# SparkFun_Artemis.net
KiCad netlist of a schematic drawn in EAGLE
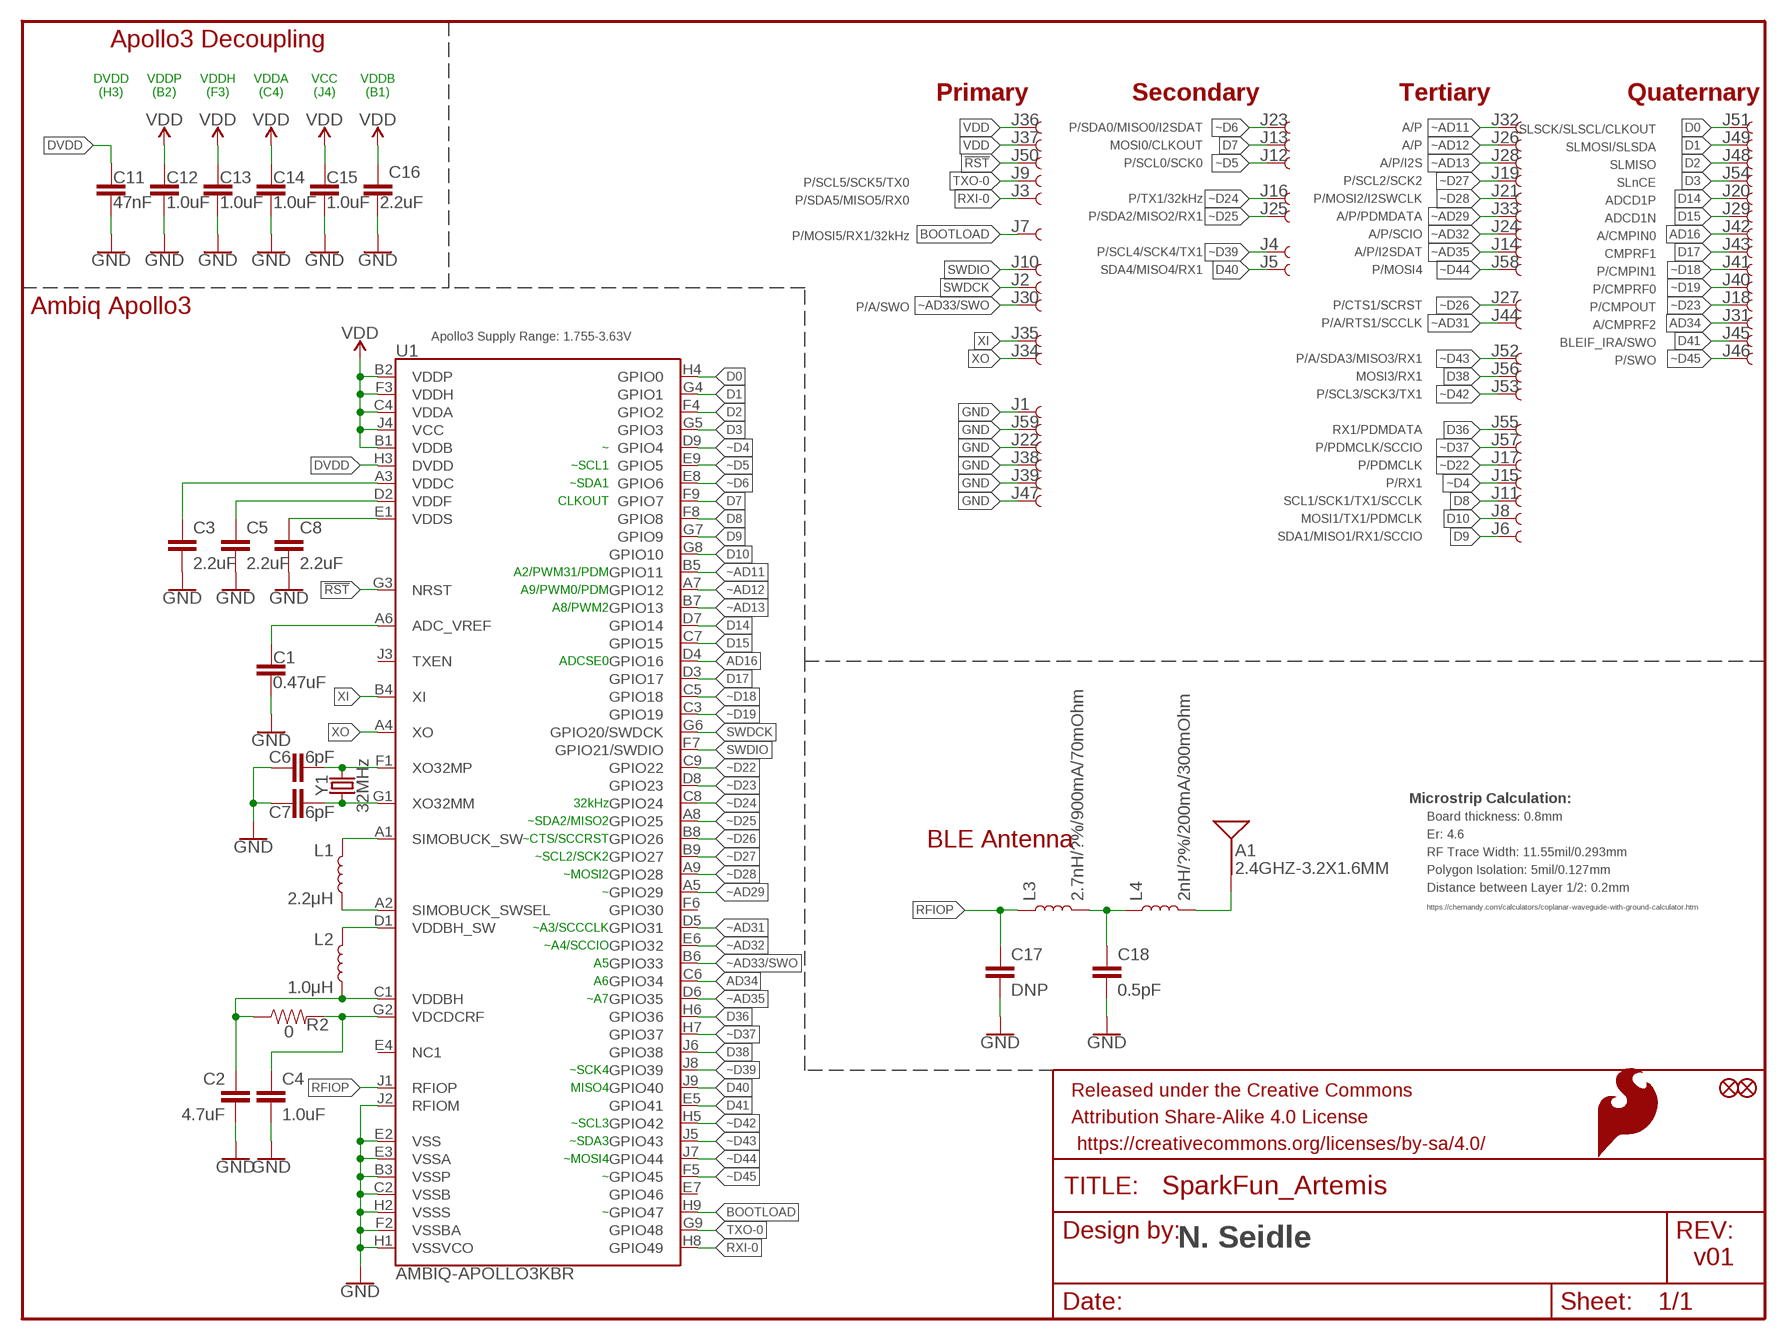
[diagram p0: schematic, sheet 1]

(export (version "E")
  (design (tool "Eeschema 10.0.6"))
  (components
    (comp (ref "A1")
      (value "2.4GHZ-3.2X1.6MM")
      (footprint "eagle-import:ANT-2.4GHZ-8.0X1.0MM")
      (libsource (lib "eagle-import") (part "ANTENNA2.4GHZ-8.0X1.0MM"))
    )
    (comp (ref "C1")
      (value "0.47uF")
      (footprint "eagle-import:0402-TIGHT")
      (libsource (lib "eagle-import") (part "470NF-0402_TIGHT-6.3V-10%-X5R"))
    )
    (comp (ref "C2")
      (value "4.7uF")
      (footprint "eagle-import:0402-TIGHT")
      (libsource (lib "eagle-import") (part "4.7UF-0402_TIGHT-6.3V-20%-X5R"))
    )
    (comp (ref "C3")
      (value "2.2uF")
      (footprint "eagle-import:0402-TIGHT")
      (libsource (lib "eagle-import") (part "2.2UF-0402_TIGHT-10V-10%-X5R"))
    )
    (comp (ref "C4")
      (value "1.0uF")
      (footprint "eagle-import:0402-TIGHT")
      (libsource (lib "eagle-import") (part "1.0UF-0402-TIGHT-16V-10%"))
    )
    (comp (ref "C5")
      (value "2.2uF")
      (footprint "eagle-import:0402-TIGHT")
      (libsource (lib "eagle-import") (part "2.2UF-0402_TIGHT-10V-10%-X5R"))
    )
    (comp (ref "C6")
      (value "6pF")
      (footprint "eagle-import:0402-TIGHT")
      (libsource (lib "eagle-import") (part "6PF-0402-TIGHT-50V-0.5%"))
    )
    (comp (ref "C7")
      (value "6pF")
      (footprint "eagle-import:0402-TIGHT")
      (libsource (lib "eagle-import") (part "6PF-0402-TIGHT-50V-0.5%"))
    )
    (comp (ref "C8")
      (value "2.2uF")
      (footprint "eagle-import:0402-TIGHT")
      (libsource (lib "eagle-import") (part "2.2UF-0402_TIGHT-10V-10%-X5R"))
    )
    (comp (ref "C11")
      (value "47nF")
      (footprint "eagle-import:0402-TIGHT")
      (libsource (lib "eagle-import") (part "47NF-0402_TIGHT-25V-10%-X7R"))
    )
    (comp (ref "C12")
      (value "1.0uF")
      (footprint "eagle-import:0402-TIGHT")
      (libsource (lib "eagle-import") (part "1.0UF-0402-TIGHT-16V-10%"))
    )
    (comp (ref "C13")
      (value "1.0uF")
      (footprint "eagle-import:0402-TIGHT")
      (libsource (lib "eagle-import") (part "1.0UF-0402-TIGHT-16V-10%"))
    )
    (comp (ref "C14")
      (value "1.0uF")
      (footprint "eagle-import:0402-TIGHT")
      (libsource (lib "eagle-import") (part "1.0UF-0402-TIGHT-16V-10%"))
    )
    (comp (ref "C15")
      (value "1.0uF")
      (footprint "eagle-import:0402-TIGHT")
      (libsource (lib "eagle-import") (part "1.0UF-0402-TIGHT-16V-10%"))
    )
    (comp (ref "C16")
      (value "2.2uF")
      (footprint "eagle-import:0402-TIGHT")
      (libsource (lib "eagle-import") (part "2.2UF-0402_TIGHT-10V-10%-X5R"))
    )
    (comp (ref "C17")
      (value "DNP")
      (footprint "eagle-import:0402-TIGHT")
      (libsource (lib "eagle-import") (part "DNP-CAP-0402-TIGHT"))
    )
    (comp (ref "C18")
      (value "0.5pF")
      (footprint "eagle-import:0402-TIGHT")
      (libsource (lib "eagle-import") (part "0.5PF-0402_TIGHT-20V-PM0.05PF-NP0"))
    )
    (comp (ref "FD3")
      (value "FIDUCIAL0.2MM")
      (footprint "eagle-import:FIDUCIAL-0.2MM")
      (libsource (lib "eagle-import") (part "FIDUCIAL0.2MM"))
    )
    (comp (ref "FD4")
      (value "FIDUCIAL0.2MM")
      (footprint "eagle-import:FIDUCIAL-0.2MM")
      (libsource (lib "eagle-import") (part "FIDUCIAL0.2MM"))
    )
    (comp (ref "FRAME1")
      (value "FRAME-LETTER")
      (footprint "eagle-import:CREATIVE_COMMONS")
      (libsource (lib "eagle-import") (part "FRAME-LETTER"))
    )
    (comp (ref "J1")
      (value "PAD.4X.6")
      (footprint "eagle-import:MODULE_PAD")
      (libsource (lib "eagle-import") (part "PAD.4X.6"))
    )
    (comp (ref "J2")
      (value "PAD.4X.6")
      (footprint "eagle-import:MODULE_PAD")
      (libsource (lib "eagle-import") (part "PAD.4X.6"))
    )
    (comp (ref "J3")
      (value "PAD.4X.6")
      (footprint "eagle-import:MODULE_PAD")
      (libsource (lib "eagle-import") (part "PAD.4X.6"))
    )
    (comp (ref "J4")
      (value "PAD.4X.6")
      (footprint "eagle-import:MODULE_PAD")
      (libsource (lib "eagle-import") (part "PAD.4X.6"))
    )
    (comp (ref "J5")
      (value "PAD.4X.6")
      (footprint "eagle-import:MODULE_PAD")
      (libsource (lib "eagle-import") (part "PAD.4X.6"))
    )
    (comp (ref "J6")
      (value "PAD.4X.6")
      (footprint "eagle-import:MODULE_PAD")
      (libsource (lib "eagle-import") (part "PAD.4X.6"))
    )
    (comp (ref "J7")
      (value "PAD.4X.6")
      (footprint "eagle-import:MODULE_PAD")
      (libsource (lib "eagle-import") (part "PAD.4X.6"))
    )
    (comp (ref "J8")
      (value "PAD.4X.6")
      (footprint "eagle-import:MODULE_PAD")
      (libsource (lib "eagle-import") (part "PAD.4X.6"))
    )
    (comp (ref "J9")
      (value "PAD.4X.6")
      (footprint "eagle-import:MODULE_PAD")
      (libsource (lib "eagle-import") (part "PAD.4X.6"))
    )
    (comp (ref "J10")
      (value "PAD.4X.6")
      (footprint "eagle-import:MODULE_PAD")
      (libsource (lib "eagle-import") (part "PAD.4X.6"))
    )
    (comp (ref "J11")
      (value "PAD.4X.6")
      (footprint "eagle-import:MODULE_PAD")
      (libsource (lib "eagle-import") (part "PAD.4X.6"))
    )
    (comp (ref "J12")
      (value "PAD.4X.6")
      (footprint "eagle-import:MODULE_PAD")
      (libsource (lib "eagle-import") (part "PAD.4X.6"))
    )
    (comp (ref "J13")
      (value "PAD.4X.6")
      (footprint "eagle-import:MODULE_PAD")
      (libsource (lib "eagle-import") (part "PAD.4X.6"))
    )
    (comp (ref "J14")
      (value "PAD.4X.6")
      (footprint "eagle-import:MODULE_PAD")
      (libsource (lib "eagle-import") (part "PAD.4X.6"))
    )
    (comp (ref "J15")
      (value "PAD.4X.6")
      (footprint "eagle-import:MODULE_PAD")
      (libsource (lib "eagle-import") (part "PAD.4X.6"))
    )
    (comp (ref "J16")
      (value "PAD.4X.6")
      (footprint "eagle-import:MODULE_PAD")
      (libsource (lib "eagle-import") (part "PAD.4X.6"))
    )
    (comp (ref "J17")
      (value "PAD.4X.6")
      (footprint "eagle-import:MODULE_PAD")
      (libsource (lib "eagle-import") (part "PAD.4X.6"))
    )
    (comp (ref "J18")
      (value "PAD.4X.6")
      (footprint "eagle-import:MODULE_PAD")
      (libsource (lib "eagle-import") (part "PAD.4X.6"))
    )
    (comp (ref "J19")
      (value "PAD.4X.6")
      (footprint "eagle-import:MODULE_PAD")
      (libsource (lib "eagle-import") (part "PAD.4X.6"))
    )
    (comp (ref "J20")
      (value "PAD.4X.6")
      (footprint "eagle-import:MODULE_PAD")
      (libsource (lib "eagle-import") (part "PAD.4X.6"))
    )
    (comp (ref "J21")
      (value "PAD.4X.6")
      (footprint "eagle-import:MODULE_PAD")
      (libsource (lib "eagle-import") (part "PAD.4X.6"))
    )
    (comp (ref "J22")
      (value "PAD.35X.35")
      (footprint "eagle-import:MODULE_MINI_PAD")
      (libsource (lib "eagle-import") (part "PAD.35X.35"))
    )
    (comp (ref "J23")
      (value "PAD.4X.6")
      (footprint "eagle-import:MODULE_PAD")
      (libsource (lib "eagle-import") (part "PAD.4X.6"))
    )
    (comp (ref "J24")
      (value "PAD.4X.6")
      (footprint "eagle-import:MODULE_PAD")
      (libsource (lib "eagle-import") (part "PAD.4X.6"))
    )
    (comp (ref "J25")
      (value "PAD.4X.6")
      (footprint "eagle-import:MODULE_PAD")
      (libsource (lib "eagle-import") (part "PAD.4X.6"))
    )
    (comp (ref "J26")
      (value "PAD.4X.6")
      (footprint "eagle-import:MODULE_PAD")
      (libsource (lib "eagle-import") (part "PAD.4X.6"))
    )
    (comp (ref "J27")
      (value "PAD.4X.6")
      (footprint "eagle-import:MODULE_PAD")
      (libsource (lib "eagle-import") (part "PAD.4X.6"))
    )
    (comp (ref "J28")
      (value "PAD.4X.6")
      (footprint "eagle-import:MODULE_PAD")
      (libsource (lib "eagle-import") (part "PAD.4X.6"))
    )
    (comp (ref "J29")
      (value "PAD.4X.6")
      (footprint "eagle-import:MODULE_PAD")
      (libsource (lib "eagle-import") (part "PAD.4X.6"))
    )
    (comp (ref "J30")
      (value "PAD.4X.6")
      (footprint "eagle-import:MODULE_PAD")
      (libsource (lib "eagle-import") (part "PAD.4X.6"))
    )
    (comp (ref "J31")
      (value "PAD.4X.6")
      (footprint "eagle-import:MODULE_PAD")
      (libsource (lib "eagle-import") (part "PAD.4X.6"))
    )
    (comp (ref "J32")
      (value "PAD.4X.6")
      (footprint "eagle-import:MODULE_PAD")
      (libsource (lib "eagle-import") (part "PAD.4X.6"))
    )
    (comp (ref "J33")
      (value "PAD.4X.6")
      (footprint "eagle-import:MODULE_PAD")
      (libsource (lib "eagle-import") (part "PAD.4X.6"))
    )
    (comp (ref "J34")
      (value "PAD.4X.6")
      (footprint "eagle-import:MODULE_PAD")
      (libsource (lib "eagle-import") (part "PAD.4X.6"))
    )
    (comp (ref "J35")
      (value "PAD.4X.6")
      (footprint "eagle-import:MODULE_PAD")
      (libsource (lib "eagle-import") (part "PAD.4X.6"))
    )
    (comp (ref "J36")
      (value "PAD.4X.6")
      (footprint "eagle-import:MODULE_PAD")
      (libsource (lib "eagle-import") (part "PAD.4X.6"))
    )
    (comp (ref "J37")
      (value "PAD.4X.6")
      (footprint "eagle-import:MODULE_PAD")
      (libsource (lib "eagle-import") (part "PAD.4X.6"))
    )
    (comp (ref "J38")
      (value "PAD.35X.35")
      (footprint "eagle-import:MODULE_MINI_PAD")
      (libsource (lib "eagle-import") (part "PAD.35X.35"))
    )
    (comp (ref "J39")
      (value "PAD.4X.6")
      (footprint "eagle-import:MODULE_PAD")
      (libsource (lib "eagle-import") (part "PAD.4X.6"))
    )
    (comp (ref "J40")
      (value "PAD.4X.6")
      (footprint "eagle-import:MODULE_PAD")
      (libsource (lib "eagle-import") (part "PAD.4X.6"))
    )
    (comp (ref "J41")
      (value "PAD.4X.6")
      (footprint "eagle-import:MODULE_PAD")
      (libsource (lib "eagle-import") (part "PAD.4X.6"))
    )
    (comp (ref "J42")
      (value "PAD.4X.6")
      (footprint "eagle-import:MODULE_PAD")
      (libsource (lib "eagle-import") (part "PAD.4X.6"))
    )
    (comp (ref "J43")
      (value "PAD.4X.6")
      (footprint "eagle-import:MODULE_PAD")
      (libsource (lib "eagle-import") (part "PAD.4X.6"))
    )
    (comp (ref "J44")
      (value "PAD.4X.6")
      (footprint "eagle-import:MODULE_PAD")
      (libsource (lib "eagle-import") (part "PAD.4X.6"))
    )
    (comp (ref "J45")
      (value "PAD.4X.6")
      (footprint "eagle-import:MODULE_PAD")
      (libsource (lib "eagle-import") (part "PAD.4X.6"))
    )
    (comp (ref "J46")
      (value "PAD.4X.6")
      (footprint "eagle-import:MODULE_PAD")
      (libsource (lib "eagle-import") (part "PAD.4X.6"))
    )
    (comp (ref "J47")
      (value "PAD.4X.6")
      (footprint "eagle-import:MODULE_PAD")
      (libsource (lib "eagle-import") (part "PAD.4X.6"))
    )
    (comp (ref "J48")
      (value "PAD.4X.6")
      (footprint "eagle-import:MODULE_PAD")
      (libsource (lib "eagle-import") (part "PAD.4X.6"))
    )
    (comp (ref "J49")
      (value "PAD.4X.6")
      (footprint "eagle-import:MODULE_PAD")
      (libsource (lib "eagle-import") (part "PAD.4X.6"))
    )
    (comp (ref "J50")
      (value "PAD.4X.6")
      (footprint "eagle-import:MODULE_PAD")
      (libsource (lib "eagle-import") (part "PAD.4X.6"))
    )
    (comp (ref "J51")
      (value "PAD.4X.6")
      (footprint "eagle-import:MODULE_PAD")
      (libsource (lib "eagle-import") (part "PAD.4X.6"))
    )
    (comp (ref "J52")
      (value "PAD.4X.6")
      (footprint "eagle-import:MODULE_PAD")
      (libsource (lib "eagle-import") (part "PAD.4X.6"))
    )
    (comp (ref "J53")
      (value "PAD.4X.6")
      (footprint "eagle-import:MODULE_PAD")
      (libsource (lib "eagle-import") (part "PAD.4X.6"))
    )
    (comp (ref "J54")
      (value "PAD.4X.6")
      (footprint "eagle-import:MODULE_PAD")
      (libsource (lib "eagle-import") (part "PAD.4X.6"))
    )
    (comp (ref "J55")
      (value "PAD.4X.6")
      (footprint "eagle-import:MODULE_PAD")
      (libsource (lib "eagle-import") (part "PAD.4X.6"))
    )
    (comp (ref "J56")
      (value "PAD.4X.6")
      (footprint "eagle-import:MODULE_PAD")
      (libsource (lib "eagle-import") (part "PAD.4X.6"))
    )
    (comp (ref "J57")
      (value "PAD.4X.6")
      (footprint "eagle-import:MODULE_PAD")
      (libsource (lib "eagle-import") (part "PAD.4X.6"))
    )
    (comp (ref "J58")
      (value "PAD.4X.6")
      (footprint "eagle-import:MODULE_PAD")
      (libsource (lib "eagle-import") (part "PAD.4X.6"))
    )
    (comp (ref "J59")
      (value "PAD.4X.6")
      (footprint "eagle-import:MODULE_PAD")
      (libsource (lib "eagle-import") (part "PAD.4X.6"))
    )
    (comp (ref "L1")
      (value "2.2μH")
      (footprint "eagle-import:0805-WIDE")
      (libsource (lib "eagle-import") (part "2.2μH-0805_WIDE-2.2μH-1.7A-0.14OHM"))
    )
    (comp (ref "L2")
      (value "1.0μH")
      (footprint "eagle-import:0805-WIDE")
      (libsource (lib "eagle-import") (part "1.0μH-0805_WIDE-1.0μH-1.45A-0.106OHM-1.0MM_H"))
    )
    (comp (ref "L3")
      (value "2.7nH/?%/900mA/70mOhm")
      (footprint "eagle-import:0402-TIGHT")
      (libsource (lib "eagle-import") (part "INDUCTOR-0402_TIGHT-2.7NH"))
    )
    (comp (ref "L4")
      (value "2nH/?%/200mA/300mOhm")
      (footprint "eagle-import:0402-TIGHT")
      (libsource (lib "eagle-import") (part "INDUCTOR-0402_TIGHT-2.0NH"))
    )
    (comp (ref "LOGO1")
      (value "SFE_LOGO_FLAME.05_INCH_INTERNAL")
      (footprint "eagle-import:SFE_LOGO_FLAME_INTERNAL_0.05")
      (libsource (lib "eagle-import") (part "SFE_LOGO_FLAME.05_INCH_INTERNAL"))
    )
    (comp (ref "R2")
      (value "0")
      (footprint "eagle-import:0402-TIGHT")
      (libsource (lib "eagle-import") (part "0OHM-0402T-1/10W"))
    )
    (comp (ref "U1")
      (value "AMBIQ-APOLLO3KBR")
      (footprint "eagle-import:BGA-81-5X5MM")
      (libsource (lib "eagle-import") (part "AMBIQ-APOLLO3KBR"))
    )
    (comp (ref "Y1")
      (value "32MHz")
      (footprint "eagle-import:CRYSTAL-SMD-2.0X1.6MM")
      (libsource (lib "eagle-import") (part "CRYSTAL-32MHZ-SMD-2.0X1.6MM"))
    )
  )
  (nets
    (net (code "1") (name "/~{AD11}") (class "Default")
      (node (ref "J32") (pin "1") (pinfunction "1_1") (pintype "bidirectional"))
      (node (ref "U1") (pin "B5") (pinfunction "GPIO11_B5") (pintype "bidirectional"))
    )
    (net (code "2") (name "/~{AD12}") (class "Default")
      (node (ref "J26") (pin "1") (pinfunction "1_1") (pintype "bidirectional"))
      (node (ref "U1") (pin "A7") (pinfunction "GPIO12_A7") (pintype "bidirectional"))
    )
    (net (code "3") (name "/~{AD13}") (class "Default")
      (node (ref "J28") (pin "1") (pinfunction "1_1") (pintype "bidirectional"))
      (node (ref "U1") (pin "B7") (pinfunction "GPIO13_B7") (pintype "bidirectional"))
    )
    (net (code "4") (name "/~{AD29}") (class "Default")
      (node (ref "J33") (pin "1") (pinfunction "1_1") (pintype "bidirectional"))
      (node (ref "U1") (pin "A5") (pinfunction "GPIO29_A5") (pintype "bidirectional"))
    )
    (net (code "5") (name "/~{AD31}") (class "Default")
      (node (ref "J44") (pin "1") (pinfunction "1_1") (pintype "bidirectional"))
      (node (ref "U1") (pin "D5") (pinfunction "GPIO31_D5") (pintype "bidirectional"))
    )
    (net (code "6") (name "/~{AD32}") (class "Default")
      (node (ref "J24") (pin "1") (pinfunction "1_1") (pintype "bidirectional"))
      (node (ref "U1") (pin "E6") (pinfunction "GPIO32_E6") (pintype "bidirectional"))
    )
    (net (code "7") (name "/~{AD33{slash}SWO}") (class "Default")
      (node (ref "J30") (pin "1") (pinfunction "1_1") (pintype "bidirectional"))
      (node (ref "U1") (pin "B6") (pinfunction "GPIO33_B6") (pintype "bidirectional"))
    )
    (net (code "8") (name "/~{AD35}") (class "Default")
      (node (ref "J14") (pin "1") (pinfunction "1_1") (pintype "bidirectional"))
      (node (ref "U1") (pin "D6") (pinfunction "GPIO35_D6") (pintype "bidirectional"))
    )
    (net (code "9") (name "/~{D4}") (class "Default")
      (node (ref "J15") (pin "1") (pinfunction "1_1") (pintype "bidirectional"))
      (node (ref "U1") (pin "D9") (pinfunction "GPIO4_D9") (pintype "bidirectional"))
    )
    (net (code "10") (name "/~{D5}") (class "Default")
      (node (ref "J12") (pin "1") (pinfunction "1_1") (pintype "bidirectional"))
      (node (ref "U1") (pin "E9") (pinfunction "GPIO5_E9") (pintype "bidirectional"))
    )
    (net (code "11") (name "/~{D6}") (class "Default")
      (node (ref "J23") (pin "1") (pinfunction "1_1") (pintype "bidirectional"))
      (node (ref "U1") (pin "E8") (pinfunction "GPIO6_E8") (pintype "bidirectional"))
    )
    (net (code "12") (name "/~{D18}") (class "Default")
      (node (ref "J41") (pin "1") (pinfunction "1_1") (pintype "bidirectional"))
      (node (ref "U1") (pin "C5") (pinfunction "GPIO18_C5") (pintype "bidirectional"))
    )
    (net (code "13") (name "/~{D19}") (class "Default")
      (node (ref "J40") (pin "1") (pinfunction "1_1") (pintype "bidirectional"))
      (node (ref "U1") (pin "C3") (pinfunction "GPIO19_C3") (pintype "bidirectional"))
    )
    (net (code "14") (name "/~{D22}") (class "Default")
      (node (ref "J17") (pin "1") (pinfunction "1_1") (pintype "bidirectional"))
      (node (ref "U1") (pin "C9") (pinfunction "GPIO22_C9") (pintype "bidirectional"))
    )
    (net (code "15") (name "/~{D23}") (class "Default")
      (node (ref "J18") (pin "1") (pinfunction "1_1") (pintype "bidirectional"))
      (node (ref "U1") (pin "D8") (pinfunction "GPIO23_D8") (pintype "bidirectional"))
    )
    (net (code "16") (name "/~{D24}") (class "Default")
      (node (ref "J16") (pin "1") (pinfunction "1_1") (pintype "bidirectional"))
      (node (ref "U1") (pin "C8") (pinfunction "GPIO24_C8") (pintype "bidirectional"))
    )
    (net (code "17") (name "/~{D25}") (class "Default")
      (node (ref "J25") (pin "1") (pinfunction "1_1") (pintype "bidirectional"))
      (node (ref "U1") (pin "A8") (pinfunction "GPIO25_A8") (pintype "bidirectional"))
    )
    (net (code "18") (name "/~{D26}") (class "Default")
      (node (ref "J27") (pin "1") (pinfunction "1_1") (pintype "bidirectional"))
      (node (ref "U1") (pin "B8") (pinfunction "GPIO26_B8") (pintype "bidirectional"))
    )
    (net (code "19") (name "/~{D27}") (class "Default")
      (node (ref "J19") (pin "1") (pinfunction "1_1") (pintype "bidirectional"))
      (node (ref "U1") (pin "B9") (pinfunction "GPIO27_B9") (pintype "bidirectional"))
    )
    (net (code "20") (name "/~{D28}") (class "Default")
      (node (ref "J21") (pin "1") (pinfunction "1_1") (pintype "bidirectional"))
      (node (ref "U1") (pin "A9") (pinfunction "GPIO28_A9") (pintype "bidirectional"))
    )
    (net (code "21") (name "/~{D37}") (class "Default")
      (node (ref "J57") (pin "1") (pinfunction "1_1") (pintype "bidirectional"))
      (node (ref "U1") (pin "H7") (pinfunction "GPIO37_H7") (pintype "bidirectional"))
    )
    (net (code "22") (name "/~{D39}") (class "Default")
      (node (ref "J4") (pin "1") (pinfunction "1_1") (pintype "bidirectional"))
      (node (ref "U1") (pin "J8") (pinfunction "GPIO39_J8") (pintype "bidirectional"))
    )
    (net (code "23") (name "/~{D42}") (class "Default")
      (node (ref "J53") (pin "1") (pinfunction "1_1") (pintype "bidirectional"))
      (node (ref "U1") (pin "H5") (pinfunction "GPIO42_H5") (pintype "bidirectional"))
    )
    (net (code "24") (name "/~{D43}") (class "Default")
      (node (ref "J52") (pin "1") (pinfunction "1_1") (pintype "bidirectional"))
      (node (ref "U1") (pin "J5") (pinfunction "GPIO43_J5") (pintype "bidirectional"))
    )
    (net (code "25") (name "/~{D44}") (class "Default")
      (node (ref "J58") (pin "1") (pinfunction "1_1") (pintype "bidirectional"))
      (node (ref "U1") (pin "J7") (pinfunction "GPIO44_J7") (pintype "bidirectional"))
    )
    (net (code "26") (name "/~{D45}") (class "Default")
      (node (ref "J46") (pin "1") (pinfunction "1_1") (pintype "bidirectional"))
      (node (ref "U1") (pin "F5") (pinfunction "GPIO45_F5") (pintype "bidirectional"))
    )
    (net (code "27") (name "/~{RST}") (class "Default")
      (node (ref "J50") (pin "1") (pinfunction "1_1") (pintype "bidirectional"))
      (node (ref "U1") (pin "G3") (pinfunction "NRST_G3") (pintype "bidirectional"))
    )
    (net (code "28") (name "AD16") (class "Default")
      (node (ref "J42") (pin "1") (pinfunction "1_1") (pintype "bidirectional"))
      (node (ref "U1") (pin "D4") (pinfunction "GPIO16_D4") (pintype "bidirectional"))
    )
    (net (code "29") (name "AD34") (class "Default")
      (node (ref "J31") (pin "1") (pinfunction "1_1") (pintype "bidirectional"))
      (node (ref "U1") (pin "C6") (pinfunction "GPIO34_C6") (pintype "bidirectional"))
    )
    (net (code "30") (name "BOOTLOAD") (class "Default")
      (node (ref "J7") (pin "1") (pinfunction "1_1") (pintype "bidirectional"))
      (node (ref "U1") (pin "H9") (pinfunction "GPIO47_H9") (pintype "bidirectional"))
    )
    (net (code "31") (name "D0") (class "Default")
      (node (ref "J51") (pin "1") (pinfunction "1_1") (pintype "bidirectional"))
      (node (ref "U1") (pin "H4") (pinfunction "GPIO0_H4") (pintype "bidirectional"))
    )
    (net (code "32") (name "D1") (class "Default")
      (node (ref "J49") (pin "1") (pinfunction "1_1") (pintype "bidirectional"))
      (node (ref "U1") (pin "G4") (pinfunction "GPIO1_G4") (pintype "bidirectional"))
    )
    (net (code "33") (name "D2") (class "Default")
      (node (ref "J48") (pin "1") (pinfunction "1_1") (pintype "bidirectional"))
      (node (ref "U1") (pin "F4") (pinfunction "GPIO2_F4") (pintype "bidirectional"))
    )
    (net (code "34") (name "D3") (class "Default")
      (node (ref "J54") (pin "1") (pinfunction "1_1") (pintype "bidirectional"))
      (node (ref "U1") (pin "G5") (pinfunction "GPIO3_G5") (pintype "bidirectional"))
    )
    (net (code "35") (name "D7") (class "Default")
      (node (ref "J13") (pin "1") (pinfunction "1_1") (pintype "bidirectional"))
      (node (ref "U1") (pin "F9") (pinfunction "GPIO7_F9") (pintype "bidirectional"))
    )
    (net (code "36") (name "D8") (class "Default")
      (node (ref "J11") (pin "1") (pinfunction "1_1") (pintype "bidirectional"))
      (node (ref "U1") (pin "F8") (pinfunction "GPIO8_F8") (pintype "bidirectional"))
    )
    (net (code "37") (name "D9") (class "Default")
      (node (ref "J6") (pin "1") (pinfunction "1_1") (pintype "bidirectional"))
      (node (ref "U1") (pin "G7") (pinfunction "GPIO9_G7") (pintype "bidirectional"))
    )
    (net (code "38") (name "D10") (class "Default")
      (node (ref "J8") (pin "1") (pinfunction "1_1") (pintype "bidirectional"))
      (node (ref "U1") (pin "G8") (pinfunction "GPIO10_G8") (pintype "bidirectional"))
    )
    (net (code "39") (name "D14") (class "Default")
      (node (ref "J20") (pin "1") (pinfunction "1_1") (pintype "bidirectional"))
      (node (ref "U1") (pin "D7") (pinfunction "GPIO14_D7") (pintype "bidirectional"))
    )
    (net (code "40") (name "D15") (class "Default")
      (node (ref "J29") (pin "1") (pinfunction "1_1") (pintype "bidirectional"))
      (node (ref "U1") (pin "C7") (pinfunction "GPIO15_C7") (pintype "bidirectional"))
    )
    (net (code "41") (name "D17") (class "Default")
      (node (ref "J43") (pin "1") (pinfunction "1_1") (pintype "bidirectional"))
      (node (ref "U1") (pin "D3") (pinfunction "GPIO17_D3") (pintype "bidirectional"))
    )
    (net (code "42") (name "D36") (class "Default")
      (node (ref "J55") (pin "1") (pinfunction "1_1") (pintype "bidirectional"))
      (node (ref "U1") (pin "H6") (pinfunction "GPIO36_H6") (pintype "bidirectional"))
    )
    (net (code "43") (name "D38") (class "Default")
      (node (ref "J56") (pin "1") (pinfunction "1_1") (pintype "bidirectional"))
      (node (ref "U1") (pin "J6") (pinfunction "GPIO38_J6") (pintype "bidirectional"))
    )
    (net (code "44") (name "D40") (class "Default")
      (node (ref "J5") (pin "1") (pinfunction "1_1") (pintype "bidirectional"))
      (node (ref "U1") (pin "J9") (pinfunction "GPIO40_J9") (pintype "bidirectional"))
    )
    (net (code "45") (name "D41") (class "Default")
      (node (ref "J45") (pin "1") (pinfunction "1_1") (pintype "bidirectional"))
      (node (ref "U1") (pin "E5") (pinfunction "GPIO41_E5") (pintype "bidirectional"))
    )
    (net (code "46") (name "DVDD") (class "Default")
      (node (ref "C11") (pin "1") (pinfunction "1_1") (pintype "passive"))
      (node (ref "U1") (pin "H3") (pinfunction "DVDD_H3") (pintype "bidirectional"))
    )
    (net (code "47") (name "GND") (class "Default")
      (node (ref "C1") (pin "2") (pinfunction "2_2") (pintype "passive"))
      (node (ref "C11") (pin "2") (pinfunction "2_2") (pintype "passive"))
      (node (ref "C12") (pin "2") (pinfunction "2_2") (pintype "passive"))
      (node (ref "C13") (pin "2") (pinfunction "2_2") (pintype "passive"))
      (node (ref "C14") (pin "2") (pinfunction "2_2") (pintype "passive"))
      (node (ref "C15") (pin "2") (pinfunction "2_2") (pintype "passive"))
      (node (ref "C16") (pin "2") (pinfunction "2_2") (pintype "passive"))
      (node (ref "C17") (pin "2") (pinfunction "2_2") (pintype "passive"))
      (node (ref "C18") (pin "2") (pinfunction "2_2") (pintype "passive"))
      (node (ref "C2") (pin "2") (pinfunction "2_2") (pintype "passive"))
      (node (ref "C3") (pin "2") (pinfunction "2_2") (pintype "passive"))
      (node (ref "C4") (pin "2") (pinfunction "2_2") (pintype "passive"))
      (node (ref "C5") (pin "2") (pinfunction "2_2") (pintype "passive"))
      (node (ref "C6") (pin "1") (pinfunction "1_1") (pintype "passive"))
      (node (ref "C7") (pin "1") (pinfunction "1_1") (pintype "passive"))
      (node (ref "C8") (pin "2") (pinfunction "2_2") (pintype "passive"))
      (node (ref "J1") (pin "1") (pinfunction "1_1") (pintype "bidirectional"))
      (node (ref "J22") (pin "1") (pinfunction "1_1") (pintype "bidirectional"))
      (node (ref "J38") (pin "1") (pinfunction "1_1") (pintype "bidirectional"))
      (node (ref "J39") (pin "1") (pinfunction "1_1") (pintype "bidirectional"))
      (node (ref "J47") (pin "1") (pinfunction "1_1") (pintype "bidirectional"))
      (node (ref "J59") (pin "1") (pinfunction "1_1") (pintype "bidirectional"))
      (node (ref "U1") (pin "B3") (pinfunction "VSSP_B3") (pintype "bidirectional"))
      (node (ref "U1") (pin "C2") (pinfunction "VSSB_C2") (pintype "bidirectional"))
      (node (ref "U1") (pin "E2") (pinfunction "VSS_E2") (pintype "bidirectional"))
      (node (ref "U1") (pin "E3") (pinfunction "VSSA_E3") (pintype "bidirectional"))
      (node (ref "U1") (pin "F2") (pinfunction "VSSBA_F2") (pintype "bidirectional"))
      (node (ref "U1") (pin "H1") (pinfunction "VSSVCO_H1") (pintype "bidirectional"))
      (node (ref "U1") (pin "H2") (pinfunction "VSSS_H2") (pintype "bidirectional"))
      (node (ref "U1") (pin "J2") (pinfunction "RFIOM_J2") (pintype "bidirectional"))
    )
    (net (code "48") (name "Net-(A1-SIGNAL)") (class "Default")
      (node (ref "A1") (pin "FEED") (pinfunction "SIGNAL_FEED") (pintype "bidirectional"))
      (node (ref "L4") (pin "2") (pinfunction "2_2") (pintype "passive"))
    )
    (net (code "49") (name "Net-(C18-Pad1)") (class "Default")
      (node (ref "C18") (pin "1") (pinfunction "1_1") (pintype "passive"))
      (node (ref "L3") (pin "2") (pinfunction "2_2") (pintype "passive"))
      (node (ref "L4") (pin "1") (pinfunction "1_1") (pintype "passive"))
    )
    (net (code "50") (name "Net-(U1-ADC_VREF)") (class "Default")
      (node (ref "C1") (pin "1") (pinfunction "1_1") (pintype "passive"))
      (node (ref "U1") (pin "A6") (pinfunction "ADC_VREF_A6") (pintype "bidirectional"))
    )
    (net (code "51") (name "Net-(U1-SIMOBUCK_SW)") (class "Default")
      (node (ref "L1") (pin "1") (pinfunction "1_1") (pintype "passive"))
      (node (ref "U1") (pin "A1") (pinfunction "SIMOBUCK_SW_A1") (pintype "bidirectional"))
    )
    (net (code "52") (name "Net-(U1-SIMOBUCK_SWSEL)") (class "Default")
      (node (ref "L1") (pin "2") (pinfunction "2_2") (pintype "passive"))
      (node (ref "U1") (pin "A2") (pinfunction "SIMOBUCK_SWSEL_A2") (pintype "bidirectional"))
    )
    (net (code "53") (name "Net-(U1-VDCDCRF)") (class "Default")
      (node (ref "C4") (pin "1") (pinfunction "1_1") (pintype "passive"))
      (node (ref "R2") (pin "2") (pinfunction "2_2") (pintype "passive"))
      (node (ref "U1") (pin "G2") (pinfunction "VDCDCRF_G2") (pintype "bidirectional"))
    )
    (net (code "54") (name "Net-(U1-VDDBH)") (class "Default")
      (node (ref "C2") (pin "1") (pinfunction "1_1") (pintype "passive"))
      (node (ref "L2") (pin "2") (pinfunction "2_2") (pintype "passive"))
      (node (ref "R2") (pin "1") (pinfunction "1_1") (pintype "passive"))
      (node (ref "U1") (pin "C1") (pinfunction "VDDBH_C1") (pintype "bidirectional"))
    )
    (net (code "55") (name "Net-(U1-VDDBH_SW)") (class "Default")
      (node (ref "L2") (pin "1") (pinfunction "1_1") (pintype "passive"))
      (node (ref "U1") (pin "D1") (pinfunction "VDDBH_SW_D1") (pintype "bidirectional"))
    )
    (net (code "56") (name "Net-(U1-VDDC)") (class "Default")
      (node (ref "C3") (pin "1") (pinfunction "1_1") (pintype "passive"))
      (node (ref "U1") (pin "A3") (pinfunction "VDDC_A3") (pintype "bidirectional"))
    )
    (net (code "57") (name "Net-(U1-VDDF)") (class "Default")
      (node (ref "C5") (pin "1") (pinfunction "1_1") (pintype "passive"))
      (node (ref "U1") (pin "D2") (pinfunction "VDDF_D2") (pintype "bidirectional"))
    )
    (net (code "58") (name "Net-(U1-VDDS)") (class "Default")
      (node (ref "C8") (pin "1") (pinfunction "1_1") (pintype "passive"))
      (node (ref "U1") (pin "E1") (pinfunction "VDDS_E1") (pintype "bidirectional"))
    )
    (net (code "59") (name "Net-(U1-XO32MM)") (class "Default")
      (node (ref "C7") (pin "2") (pinfunction "2_2") (pintype "passive"))
      (node (ref "U1") (pin "G1") (pinfunction "XO32MM_G1") (pintype "bidirectional"))
      (node (ref "Y1") (pin "1") (pinfunction "1_1") (pintype "passive"))
    )
    (net (code "60") (name "Net-(U1-XO32MP)") (class "Default")
      (node (ref "C6") (pin "2") (pinfunction "2_2") (pintype "passive"))
      (node (ref "U1") (pin "F1") (pinfunction "XO32MP_F1") (pintype "bidirectional"))
      (node (ref "Y1") (pin "3") (pinfunction "2_3") (pintype "passive"))
    )
    (net (code "61") (name "RFIOP") (class "Default")
      (node (ref "C17") (pin "1") (pinfunction "1_1") (pintype "passive"))
      (node (ref "L3") (pin "1") (pinfunction "1_1") (pintype "passive"))
      (node (ref "U1") (pin "J1") (pinfunction "RFIOP_J1") (pintype "bidirectional"))
    )
    (net (code "62") (name "RXI-0") (class "Default")
      (node (ref "J3") (pin "1") (pinfunction "1_1") (pintype "bidirectional"))
      (node (ref "U1") (pin "H8") (pinfunction "GPIO49_H8") (pintype "bidirectional"))
    )
    (net (code "63") (name "SWDCK") (class "Default")
      (node (ref "J2") (pin "1") (pinfunction "1_1") (pintype "bidirectional"))
      (node (ref "U1") (pin "G6") (pinfunction "GPIO20/SWDCK_G6") (pintype "bidirectional"))
    )
    (net (code "64") (name "SWDIO") (class "Default")
      (node (ref "J10") (pin "1") (pinfunction "1_1") (pintype "bidirectional"))
      (node (ref "U1") (pin "F7") (pinfunction "GPIO21/SWDIO_F7") (pintype "bidirectional"))
    )
    (net (code "65") (name "TXO-0") (class "Default")
      (node (ref "J9") (pin "1") (pinfunction "1_1") (pintype "bidirectional"))
      (node (ref "U1") (pin "G9") (pinfunction "GPIO48_G9") (pintype "bidirectional"))
    )
    (net (code "66") (name "VDD") (class "Default")
      (node (ref "C12") (pin "1") (pinfunction "1_1") (pintype "passive"))
      (node (ref "C13") (pin "1") (pinfunction "1_1") (pintype "passive"))
      (node (ref "C14") (pin "1") (pinfunction "1_1") (pintype "passive"))
      (node (ref "C15") (pin "1") (pinfunction "1_1") (pintype "passive"))
      (node (ref "C16") (pin "1") (pinfunction "1_1") (pintype "passive"))
      (node (ref "J36") (pin "1") (pinfunction "1_1") (pintype "bidirectional"))
      (node (ref "J37") (pin "1") (pinfunction "1_1") (pintype "bidirectional"))
      (node (ref "U1") (pin "B1") (pinfunction "VDDB_B1") (pintype "bidirectional"))
      (node (ref "U1") (pin "B2") (pinfunction "VDDP_B2") (pintype "bidirectional"))
      (node (ref "U1") (pin "C4") (pinfunction "VDDA_C4") (pintype "bidirectional"))
      (node (ref "U1") (pin "F3") (pinfunction "VDDH_F3") (pintype "bidirectional"))
      (node (ref "U1") (pin "J4") (pinfunction "VCC_J4") (pintype "bidirectional"))
    )
    (net (code "67") (name "XI") (class "Default")
      (node (ref "J35") (pin "1") (pinfunction "1_1") (pintype "bidirectional"))
      (node (ref "U1") (pin "B4") (pinfunction "XI_B4") (pintype "bidirectional"))
    )
    (net (code "68") (name "XO") (class "Default")
      (node (ref "J34") (pin "1") (pinfunction "1_1") (pintype "bidirectional"))
      (node (ref "U1") (pin "A4") (pinfunction "XO_A4") (pintype "bidirectional"))
    )
    (net (code "69") (name "unconnected-(U1-GPIO30-PadF6)") (class "Default")
      (node (ref "U1") (pin "F6") (pinfunction "GPIO30_F6") (pintype "bidirectional"))
    )
    (net (code "70") (name "unconnected-(U1-GPIO46-PadE7)") (class "Default")
      (node (ref "U1") (pin "E7") (pinfunction "GPIO46_E7") (pintype "bidirectional"))
    )
    (net (code "71") (name "unconnected-(U1-NC1-PadE4)") (class "Default")
      (node (ref "U1") (pin "E4") (pinfunction "NC1_E4") (pintype "bidirectional"))
    )
    (net (code "72") (name "unconnected-(U1-TXEN-PadJ3)") (class "Default")
      (node (ref "U1") (pin "J3") (pinfunction "TXEN_J3") (pintype "bidirectional"))
    )
  )
)
